# ForEK2.net
KiCad netlist of a schematic drawn in Altium Designer
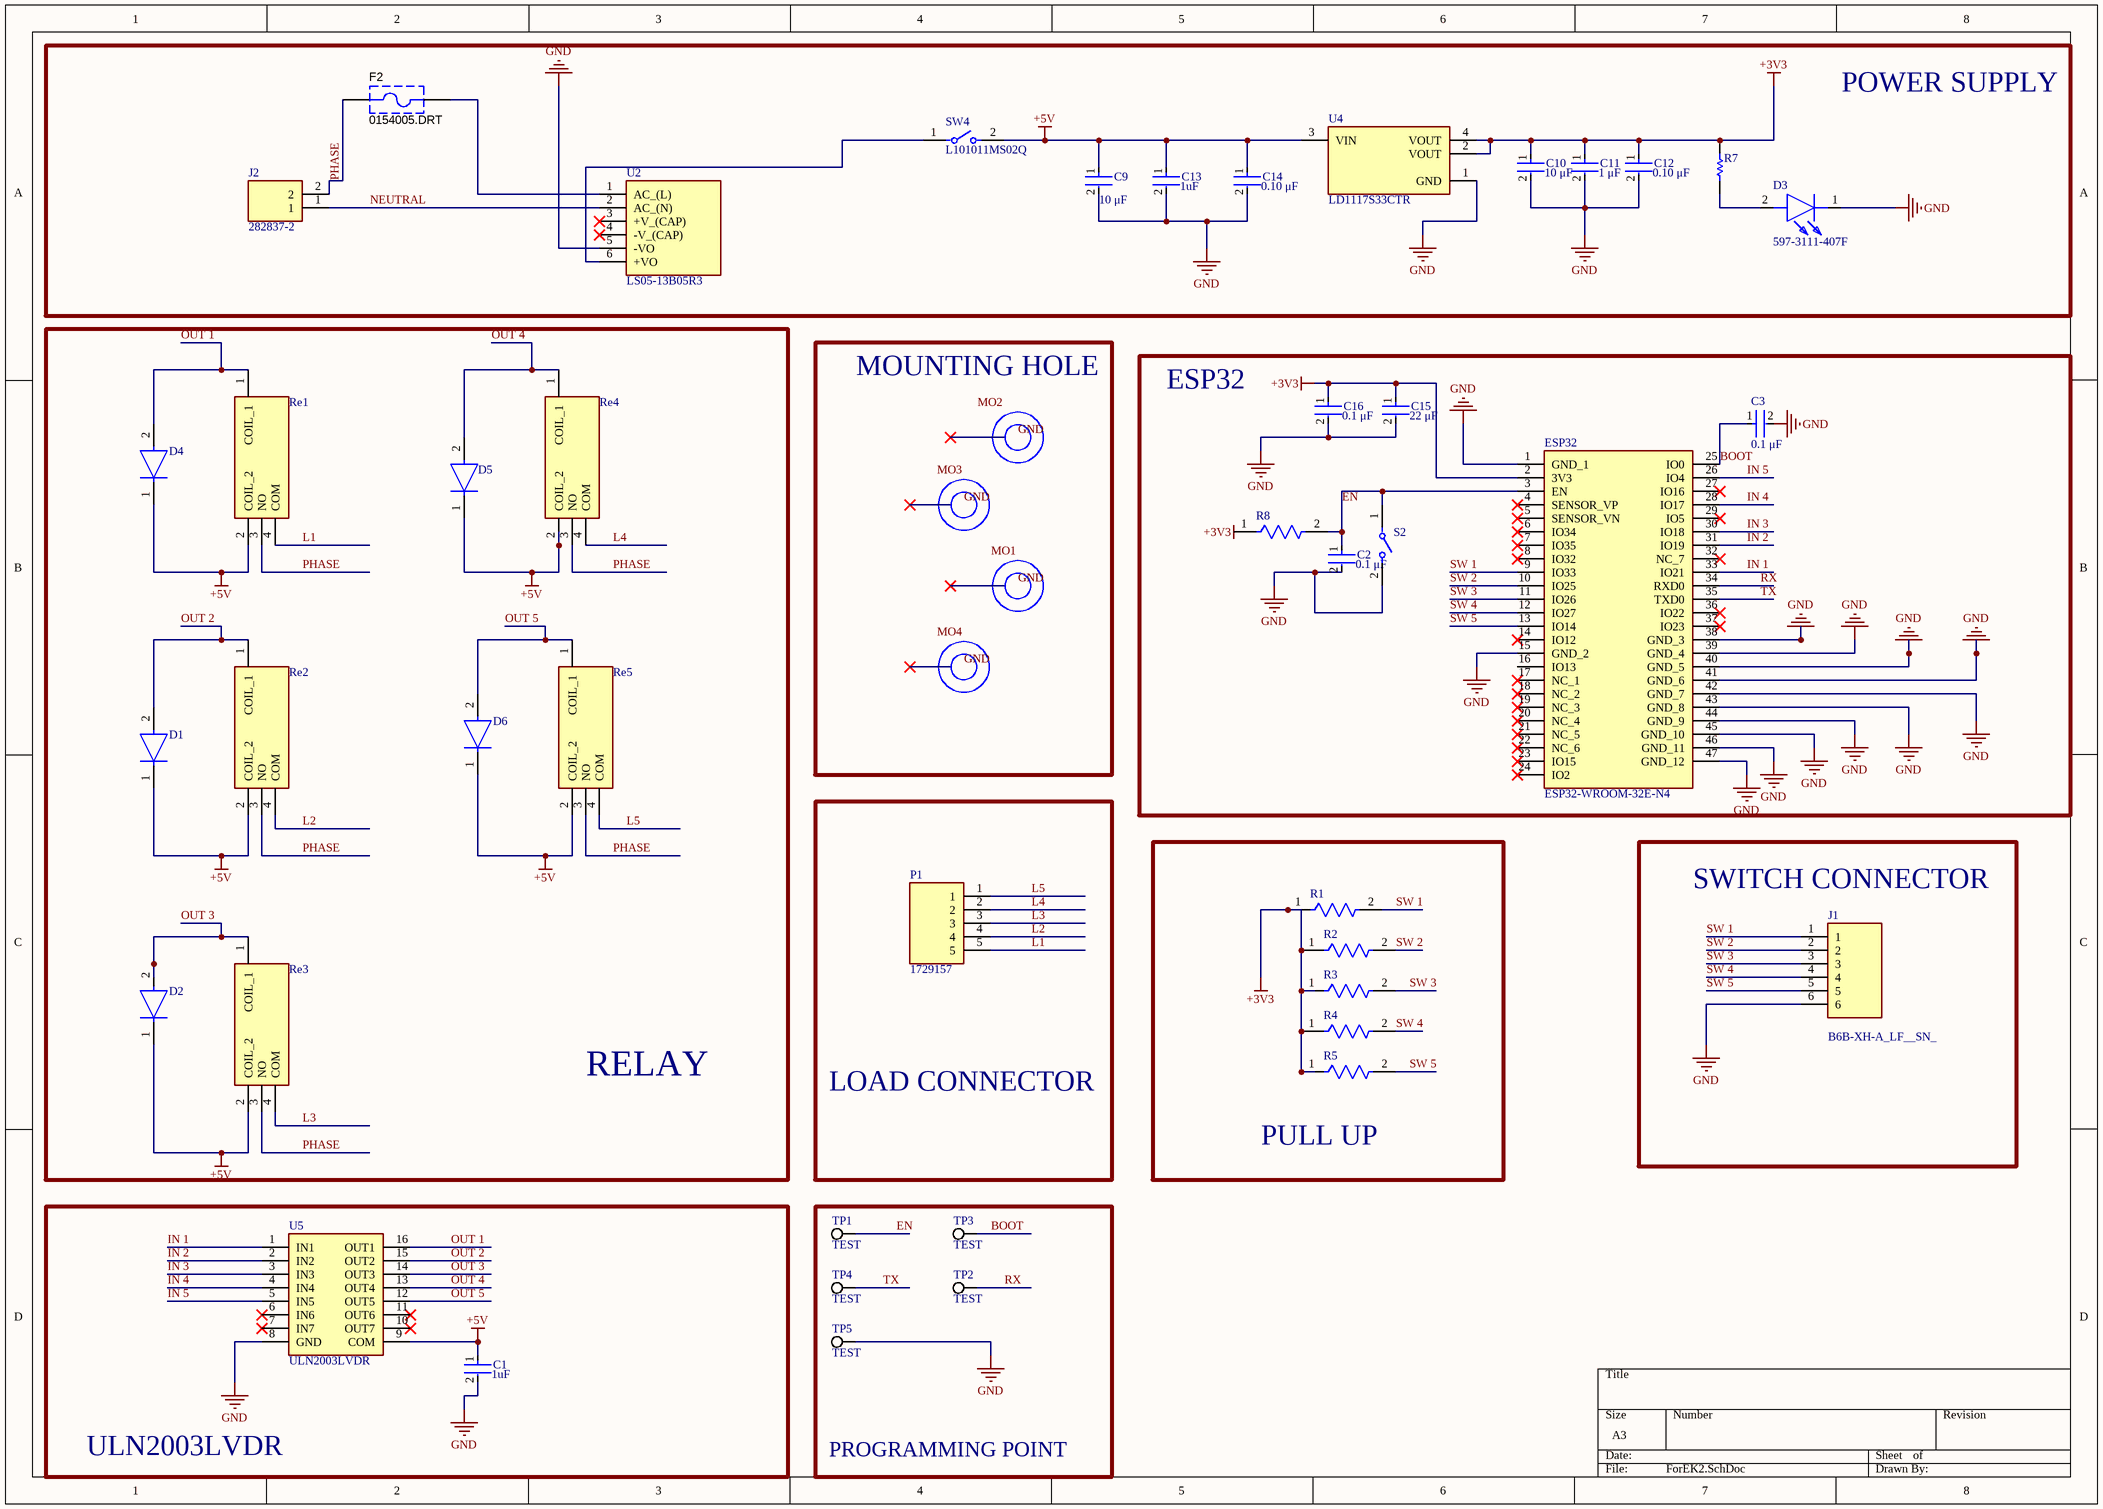
[diagram p0: ForEK2.SchDoc]

(export (version "E")
  (design (tool "Eeschema 10.0.6"))
  (components
    (comp (ref "C1")
      (value "C0402C104K8PACTU")
      (footprint "FP-C0402-BB-MFG")
      (description "CAP CER 0.1UF 10V X5R 0402")
      (fields
        (field (name "CAPACITANCE") "1uF")
        (field (name "MANUFACTURER") "Kemet")
        (field (name "TOLERANCE") "0.1")
      )
      (libsource (lib "Altium Content Vault") (part "b4654b650e69147ec39a6b967a45e02"))
    )
    (comp (ref "C2")
      (value "0.1 μF")
      (footprint "FP-C0402-BB-MFG")
      (description "CAP CER 0.1UF 10V X5R 0402")
      (fields (field (name "MANUFACTURER") "Kemet") (field (name "TOLERANCE") "0.1"))
      (libsource (lib "Altium Content Vault") (part "b4654b650e69147ec39a6b967a45e02"))
    )
    (comp (ref "C3")
      (value "0.1 μF")
      (footprint "FP-C0402-BB-MFG")
      (description "CAP CER 0.1UF 10V X5R 0402")
      (fields (field (name "MANUFACTURER") "Kemet") (field (name "TOLERANCE") "0.1"))
      (libsource (lib "Altium Content Vault") (part "b4654b650e69147ec39a6b967a45e02"))
    )
    (comp (ref "C9")
      (value "10 μF")
      (footprint "FP-C0402-BB-MFG")
      (description "CAP CER 0.1UF 10V X5R 0402")
      (fields (field (name "MANUFACTURER") "Kemet") (field (name "TOLERANCE") "0.1"))
      (libsource (lib "Altium Content Vault") (part "b4654b650e69147ec39a6b967a45e02"))
    )
    (comp (ref "C10")
      (value "10 μF")
      (footprint "FP-C0402-BB-MFG")
      (description "CAP CER 0.1UF 10V X5R 0402")
      (fields (field (name "MANUFACTURER") "Kemet") (field (name "TOLERANCE") "0.1"))
      (libsource (lib "Altium Content Vault") (part "b4654b650e69147ec39a6b967a45e02"))
    )
    (comp (ref "C11")
      (value "1 μF")
      (footprint "FP-C0402-BB-MFG")
      (description "CAP CER 0.1UF 10V X5R 0402")
      (fields (field (name "MANUFACTURER") "Kemet") (field (name "TOLERANCE") "0.1"))
      (libsource (lib "Altium Content Vault") (part "b4654b650e69147ec39a6b967a45e02"))
    )
    (comp (ref "C12")
      (value "C0402C104K8PACTU")
      (footprint "FP-C0402-BB-MFG")
      (description "CAP CER 0.1UF 10V X5R 0402")
      (fields
        (field (name "CAPACITANCE") "0.10 μF")
        (field (name "MANUFACTURER") "Kemet")
        (field (name "TOLERANCE") "0.1")
      )
      (libsource (lib "Altium Content Vault") (part "b4654b650e69147ec39a6b967a45e02"))
    )
    (comp (ref "C13")
      (value "C0402C104K8PACTU")
      (footprint "FP-C0402-BB-MFG")
      (description "CAP CER 0.1UF 10V X5R 0402")
      (fields
        (field (name "CAPACITANCE") "1uF")
        (field (name "MANUFACTURER") "Kemet")
        (field (name "TOLERANCE") "0.1")
      )
      (libsource (lib "Altium Content Vault") (part "b4654b650e69147ec39a6b967a45e02"))
    )
    (comp (ref "C14")
      (value "0.10 μF")
      (footprint "FP-C0402-BB-MFG")
      (description "CAP CER 0.1UF 10V X5R 0402")
      (fields (field (name "MANUFACTURER") "Kemet") (field (name "TOLERANCE") "0.1"))
      (libsource (lib "Altium Content Vault") (part "b4654b650e69147ec39a6b967a45e02"))
    )
    (comp (ref "C15")
      (value "22 μF")
      (footprint "FP-C0402-BB-MFG")
      (description "CAP CER 0.1UF 10V X5R 0402")
      (fields (field (name "MANUFACTURER") "Kemet") (field (name "TOLERANCE") "0.1"))
      (libsource (lib "Altium Content Vault") (part "b4654b650e69147ec39a6b967a45e02"))
    )
    (comp (ref "C16")
      (value "0.1 μF")
      (footprint "FP-C0402-BB-MFG")
      (description "CAP CER 0.1UF 10V X5R 0402")
      (fields (field (name "MANUFACTURER") "Kemet") (field (name "TOLERANCE") "0.1"))
      (libsource (lib "Altium Content Vault") (part "b4654b650e69147ec39a6b967a45e02"))
    )
    (comp (ref "D1")
      (value "1N4148")
      (footprint "FP-017AG-MFG")
      (description "DIODE GEN PURP 100V 200MA DO35")
      (fields (field (name "VOLTAGE") "100V"))
      (libsource (lib "Altium Content Vault") (part "d7152d700b627762746794eb795d46e"))
    )
    (comp (ref "D2")
      (value "1N4148")
      (footprint "FP-017AG-MFG")
      (description "DIODE GEN PURP 100V 200MA DO35")
      (fields (field (name "VOLTAGE") "100V"))
      (libsource (lib "Altium Content Vault") (part "d7152d700b627762746794eb795d46e"))
    )
    (comp (ref "D3")
      (value "597-3111-407F")
      (footprint "SamacSys:LEDC3015X150N")
      (description "LED")
      (fields (field (name "MOUSER PART NUMBER") "645-597-3111-407F"))
      (libsource (lib "*") (part "597-3111-407F"))
    )
    (comp (ref "D4")
      (value "1N4148")
      (footprint "FP-017AG-MFG")
      (description "DIODE GEN PURP 100V 200MA DO35")
      (fields (field (name "VOLTAGE") "100V"))
      (libsource (lib "Altium Content Vault") (part "d7152d700b627762746794eb795d46e"))
    )
    (comp (ref "D5")
      (value "1N4148")
      (footprint "FP-017AG-MFG")
      (description "DIODE GEN PURP 100V 200MA DO35")
      (fields (field (name "VOLTAGE") "100V"))
      (libsource (lib "Altium Content Vault") (part "d7152d700b627762746794eb795d46e"))
    )
    (comp (ref "D6")
      (value "1N4148")
      (footprint "FP-017AG-MFG")
      (description "DIODE GEN PURP 100V 200MA DO35")
      (fields (field (name "VOLTAGE") "100V"))
      (libsource (lib "Altium Content Vault") (part "d7152d700b627762746794eb795d46e"))
    )
    (comp (ref "ESP32")
      (value "ESP32-WROOM-32E-N4")
      (footprint "SamacSys:ESP32WROOM32EN4")
      (description "Integrated Circuit")
      (fields (field (name "MOUSER PART NUMBER") "356-ESP32WRM32E132PH"))
      (libsource (lib "*") (part "ESP32-WROOM-32E-N4"))
    )
    (comp (ref "F2")
      (value "0154005.DRT")
      (footprint "LFUS-154_V")
      (description "Fuse and Holder Combination, 125 V, 5 A, -55 to 125 degC, 2-Pin SMD, RoHS, Tape and Reel")
      (fields (field (name "MANUFACTURER") "Littelfuse"))
      (libsource (lib "Altium Content Vault") (part "FUSE_HOLDER-2"))
    )
    (comp (ref "J1")
      (value "B6B-XH-A_LF__SN_")
      (footprint "SamacSys:SHDR6W64P0X250_1X6_1740X575X700P")
      (description "Connector")
      (fields
        (field (name "MANUFACTURER_PART_NUMBER") "B6B-XH-A(LF)(SN)")
        (field (name "MOUSER PART NUMBER") "306-B6BXHALFSN")
      )
      (libsource (lib "*") (part "B6B-XH-A_LF__SN_"))
    )
    (comp (ref "J2")
      (value "282837-2")
      (footprint "SamacSys:2828372")
      (description "Connector")
      (fields (field (name "MOUSER PART NUMBER") "571-2828372"))
      (libsource (lib "*") (part "282837-2"))
    )
    (comp (ref "P1")
      (value "1729157")
      (footprint "SamacSys:1729157")
      (description "Connector")
      (fields (field (name "MOUSER PART NUMBER") "651-1729157"))
      (libsource (lib "*") (part "1729157"))
    )
    (comp (ref "R1")
      (value "CRCW040210K0JNED")
      (footprint "FP-CRCW0402-e3-IPC_B")
      (description "RES Thick Film, 10kΩ, 5%, 0.063W, 200ppm/°C, 0402")
      (fields (field (name "TOLERANCE") "5%"))
      (libsource (lib "Altium Content Vault") (part "1029c3af85768c4190bb7ad29bc67b5"))
    )
    (comp (ref "R2")
      (value "CRCW040210K0JNED")
      (footprint "FP-CRCW0402-e3-IPC_B")
      (description "RES Thick Film, 10kΩ, 5%, 0.063W, 200ppm/°C, 0402")
      (fields (field (name "TOLERANCE") "5%"))
      (libsource (lib "Altium Content Vault") (part "1029c3af85768c4190bb7ad29bc67b5"))
    )
    (comp (ref "R3")
      (value "CRCW040210K0JNED")
      (footprint "FP-CRCW0402-e3-IPC_B")
      (description "RES Thick Film, 10kΩ, 5%, 0.063W, 200ppm/°C, 0402")
      (fields (field (name "TOLERANCE") "5%"))
      (libsource (lib "Altium Content Vault") (part "1029c3af85768c4190bb7ad29bc67b5"))
    )
    (comp (ref "R4")
      (value "CRCW040210K0JNED")
      (footprint "FP-CRCW0402-e3-IPC_B")
      (description "RES Thick Film, 10kΩ, 5%, 0.063W, 200ppm/°C, 0402")
      (fields (field (name "TOLERANCE") "5%"))
      (libsource (lib "Altium Content Vault") (part "1029c3af85768c4190bb7ad29bc67b5"))
    )
    (comp (ref "R5")
      (value "CRCW040210K0JNED")
      (footprint "FP-CRCW0402-e3-IPC_B")
      (description "RES Thick Film, 10kΩ, 5%, 0.063W, 200ppm/°C, 0402")
      (fields (field (name "TOLERANCE") "5%"))
      (libsource (lib "Altium Content Vault") (part "1029c3af85768c4190bb7ad29bc67b5"))
    )
    (comp (ref "R7")
      (value "ERJ-3EKF3300V")
      (footprint "RESC1608X55X30LL15T15")
      (description "Chip Resistor, 330 Ohm, +/- 1%, 0.1 W, -55 to 155 degC, 0603 (1608 Metric), RoHS, Tape and Reel")
      (libsource (lib "Altium Content Vault") (part "RES-2"))
    )
    (comp (ref "R8")
      (value "CRCW040210K0JNED")
      (footprint "FP-CRCW0402-e3-IPC_B")
      (description "RES Thick Film, 10kΩ, 5%, 0.063W, 200ppm/°C, 0402")
      (fields (field (name "TOLERANCE") "5%"))
      (libsource (lib "Altium Content Vault") (part "1029c3af85768c4190bb7ad29bc67b5"))
    )
    (comp (ref "Re1")
      (value "HF46F-G_5-HS1T")
      (footprint "SamacSys:HF46FG5HS1T")
      (description "Relay or Contactor")
      (fields (field (name "MANUFACTURER_PART_NUMBER") "HF46F-G/5-HS1T"))
      (libsource (lib "*") (part "HF46F-G_5-HS1T"))
    )
    (comp (ref "Re2")
      (value "HF46F-G_5-HS1T")
      (footprint "SamacSys:HF46FG5HS1T")
      (description "Relay or Contactor")
      (fields (field (name "MANUFACTURER_PART_NUMBER") "HF46F-G/5-HS1T"))
      (libsource (lib "*") (part "HF46F-G_5-HS1T"))
    )
    (comp (ref "Re3")
      (value "HF46F-G_5-HS1T")
      (footprint "SamacSys:HF46FG5HS1T")
      (description "Relay or Contactor")
      (fields (field (name "MANUFACTURER_PART_NUMBER") "HF46F-G/5-HS1T"))
      (libsource (lib "*") (part "HF46F-G_5-HS1T"))
    )
    (comp (ref "Re4")
      (value "HF46F-G_5-HS1T")
      (footprint "SamacSys:HF46FG5HS1T")
      (description "Relay or Contactor")
      (fields (field (name "MANUFACTURER_PART_NUMBER") "HF46F-G/5-HS1T"))
      (libsource (lib "*") (part "HF46F-G_5-HS1T"))
    )
    (comp (ref "Re5")
      (value "HF46F-G_5-HS1T")
      (footprint "SamacSys:HF46FG5HS1T")
      (description "Relay or Contactor")
      (fields (field (name "MANUFACTURER_PART_NUMBER") "HF46F-G/5-HS1T"))
      (libsource (lib "*") (part "HF46F-G_5-HS1T"))
    )
    (comp (ref "S2")
      (value "L101011MS02Q")
      (footprint "FP-L101011MS02Q-MFG")
      (description "SWITCH SLIDE SPST 4A 125V")
      (libsource (lib "Altium Content Vault") (part "bb27bde45df87f1f469753f287ef5ae"))
    )
    (comp (ref "SW4")
      (value "L101011MS02Q")
      (footprint "FP-L101011MS02Q-MFG")
      (description "SWITCH SLIDE SPST 4A 125V")
      (libsource (lib "Altium Content Vault") (part "bb27bde45df87f1f469753f287ef5ae"))
    )
    (comp (ref "TP1")
      (value "TEST")
      (footprint "KSTN-5012_V")
      (description "Test Point, White, Through Hole, RoHS, Bulk")
      (fields (field (name "MANUFACTURER") "Keystone"))
      (libsource (lib "Altium Content Vault") (part "TESTPOINT_WHITE"))
    )
    (comp (ref "TP2")
      (value "TEST")
      (footprint "KSTN-5012_V")
      (description "Test Point, White, Through Hole, RoHS, Bulk")
      (fields (field (name "MANUFACTURER") "Keystone"))
      (libsource (lib "Altium Content Vault") (part "TESTPOINT_WHITE"))
    )
    (comp (ref "TP3")
      (value "TEST")
      (footprint "KSTN-5012_V")
      (description "Test Point, White, Through Hole, RoHS, Bulk")
      (fields (field (name "MANUFACTURER") "Keystone"))
      (libsource (lib "Altium Content Vault") (part "TESTPOINT_WHITE"))
    )
    (comp (ref "TP4")
      (value "TEST")
      (footprint "KSTN-5012_V")
      (description "Test Point, White, Through Hole, RoHS, Bulk")
      (fields (field (name "MANUFACTURER") "Keystone"))
      (libsource (lib "Altium Content Vault") (part "TESTPOINT_WHITE"))
    )
    (comp (ref "TP5")
      (value "TEST")
      (footprint "KSTN-5012_V")
      (description "Test Point, White, Through Hole, RoHS, Bulk")
      (fields (field (name "MANUFACTURER") "Keystone"))
      (libsource (lib "Altium Content Vault") (part "TESTPOINT_WHITE"))
    )
    (comp (ref "U2")
      (value "LS05-13B05R3")
      (footprint "SamacSys:LS0513B05R3")
      (description "Power Supply")
      (libsource (lib "*") (part "LS05-13B05R3"))
    )
    (comp (ref "U4")
      (value "LD1117S33CTR")
      (footprint "FP-SOT-223-0046067_14-MFG")
      (description "IC REG LINEAR 3.3V 800MA SOT223")
      (libsource (lib "Altium Content Vault") (part "7818869c5c16ceab15634627166a29d"))
    )
    (comp (ref "U5")
      (value "ULN2003LVDR")
      (footprint "SamacSys:SOIC127P600X175-16N")
      (description "Integrated Circuit")
      (fields (field (name "MOUSER PART NUMBER") "595-ULN2003LVDR"))
      (libsource (lib "*") (part "ULN2003LVDR"))
    )
  )
  (nets
    (net (code "1") (name "+3V3") (class "Default")
      (node (ref "C10") (pin "1") (pinfunction "1_1") (pintype "passive"))
      (node (ref "C11") (pin "1") (pinfunction "1_1") (pintype "passive"))
      (node (ref "C12") (pin "1") (pinfunction "1_1") (pintype "passive"))
      (node (ref "C15") (pin "1") (pinfunction "1_1") (pintype "passive"))
      (node (ref "C16") (pin "1") (pinfunction "1_1") (pintype "passive"))
      (node (ref "ESP32") (pin "2") (pinfunction "3V3_2") (pintype "passive"))
      (node (ref "R1") (pin "1") (pinfunction "1_1") (pintype "passive"))
      (node (ref "R2") (pin "1") (pinfunction "1_1") (pintype "passive"))
      (node (ref "R3") (pin "1") (pinfunction "1_1") (pintype "passive"))
      (node (ref "R4") (pin "1") (pinfunction "1_1") (pintype "passive"))
      (node (ref "R5") (pin "1") (pinfunction "1_1") (pintype "passive"))
      (node (ref "R7") (pin "2") (pinfunction "2_2") (pintype "passive"))
      (node (ref "U4") (pin "2") (pinfunction "VOUT_2") (pintype "power_in"))
      (node (ref "U4") (pin "4") (pinfunction "VOUT_4") (pintype "power_in"))
    )
    (net (code "2") (name "+5V") (class "Default")
      (node (ref "C1") (pin "1") (pinfunction "1_1") (pintype "passive"))
      (node (ref "C13") (pin "1") (pinfunction "1_1") (pintype "passive"))
      (node (ref "C14") (pin "1") (pinfunction "1_1") (pintype "passive"))
      (node (ref "C9") (pin "1") (pinfunction "1_1") (pintype "passive"))
      (node (ref "D1") (pin "1") (pinfunction "C_1") (pintype "passive"))
      (node (ref "D2") (pin "1") (pinfunction "C_1") (pintype "passive"))
      (node (ref "D4") (pin "1") (pinfunction "C_1") (pintype "passive"))
      (node (ref "D5") (pin "1") (pinfunction "C_1") (pintype "passive"))
      (node (ref "D6") (pin "1") (pinfunction "C_1") (pintype "passive"))
      (node (ref "Re1") (pin "2") (pinfunction "COIL_2_2") (pintype "passive"))
      (node (ref "Re2") (pin "2") (pinfunction "COIL_2_2") (pintype "passive"))
      (node (ref "Re3") (pin "2") (pinfunction "COIL_2_2") (pintype "passive"))
      (node (ref "Re4") (pin "2") (pinfunction "COIL_2_2") (pintype "passive"))
      (node (ref "Re5") (pin "2") (pinfunction "COIL_2_2") (pintype "passive"))
      (node (ref "SW4") (pin "2") (pinfunction "2_2") (pintype "passive"))
      (node (ref "U4") (pin "3") (pinfunction "VIN_3") (pintype "power_in"))
      (node (ref "U5") (pin "9") (pinfunction "COM_9") (pintype "passive"))
    )
    (net (code "3") (name "/BOOT") (class "Default")
      (node (ref "C3") (pin "1") (pinfunction "1_1") (pintype "passive"))
      (node (ref "ESP32") (pin "25") (pinfunction "IO0_25") (pintype "passive"))
      (node (ref "TP3") (pin "1") (pinfunction "1_1") (pintype "passive"))
    )
    (net (code "4") (name "/EN") (class "Default")
      (node (ref "C2") (pin "1") (pinfunction "1_1") (pintype "passive"))
      (node (ref "ESP32") (pin "3") (pinfunction "EN_3") (pintype "passive"))
      (node (ref "R8") (pin "2") (pinfunction "2_2") (pintype "passive"))
      (node (ref "S2") (pin "1") (pinfunction "1_1") (pintype "passive"))
      (node (ref "TP1") (pin "1") (pinfunction "1_1") (pintype "passive"))
    )
    (net (code "5") (name "/IN 1") (class "Default")
      (node (ref "ESP32") (pin "33") (pinfunction "IO21_33") (pintype "passive"))
      (node (ref "U5") (pin "1") (pinfunction "IN1_1") (pintype "passive"))
    )
    (net (code "6") (name "/IN 2") (class "Default")
      (node (ref "ESP32") (pin "31") (pinfunction "IO19_31") (pintype "passive"))
      (node (ref "U5") (pin "2") (pinfunction "IN2_2") (pintype "passive"))
    )
    (net (code "7") (name "/IN 3") (class "Default")
      (node (ref "ESP32") (pin "30") (pinfunction "IO18_30") (pintype "passive"))
      (node (ref "U5") (pin "3") (pinfunction "IN3_3") (pintype "passive"))
    )
    (net (code "8") (name "/IN 4") (class "Default")
      (node (ref "ESP32") (pin "28") (pinfunction "IO17_28") (pintype "passive"))
      (node (ref "U5") (pin "4") (pinfunction "IN4_4") (pintype "passive"))
    )
    (net (code "9") (name "/IN 5") (class "Default")
      (node (ref "ESP32") (pin "26") (pinfunction "IO4_26") (pintype "passive"))
      (node (ref "U5") (pin "5") (pinfunction "IN5_5") (pintype "passive"))
    )
    (net (code "10") (name "/L1") (class "Default")
      (node (ref "P1") (pin "5") (pinfunction "5_5") (pintype "passive"))
      (node (ref "Re1") (pin "4") (pinfunction "COM_4") (pintype "passive"))
    )
    (net (code "11") (name "/L2") (class "Default")
      (node (ref "P1") (pin "4") (pinfunction "4_4") (pintype "passive"))
      (node (ref "Re2") (pin "4") (pinfunction "COM_4") (pintype "passive"))
    )
    (net (code "12") (name "/L3") (class "Default")
      (node (ref "P1") (pin "3") (pinfunction "3_3") (pintype "passive"))
      (node (ref "Re3") (pin "4") (pinfunction "COM_4") (pintype "passive"))
    )
    (net (code "13") (name "/L4") (class "Default")
      (node (ref "P1") (pin "2") (pinfunction "2_2") (pintype "passive"))
      (node (ref "Re4") (pin "4") (pinfunction "COM_4") (pintype "passive"))
    )
    (net (code "14") (name "/L5") (class "Default")
      (node (ref "P1") (pin "1") (pinfunction "1_1") (pintype "passive"))
      (node (ref "Re5") (pin "4") (pinfunction "COM_4") (pintype "passive"))
    )
    (net (code "19") (name "/NEUTRAL") (class "Default")
      (node (ref "J2") (pin "1") (pinfunction "1_1") (pintype "passive"))
      (node (ref "U2") (pin "2") (pinfunction "AC_(N)_2") (pintype "passive"))
    )
    (net (code "20") (name "/OUT 1") (class "Default")
      (node (ref "D4") (pin "2") (pinfunction "A_2") (pintype "passive"))
      (node (ref "Re1") (pin "1") (pinfunction "COIL_1_1") (pintype "passive"))
      (node (ref "U5") (pin "16") (pinfunction "OUT1_16") (pintype "passive"))
    )
    (net (code "21") (name "/OUT 2") (class "Default")
      (node (ref "D1") (pin "2") (pinfunction "A_2") (pintype "passive"))
      (node (ref "Re2") (pin "1") (pinfunction "COIL_1_1") (pintype "passive"))
      (node (ref "U5") (pin "15") (pinfunction "OUT2_15") (pintype "passive"))
    )
    (net (code "22") (name "/OUT 3") (class "Default")
      (node (ref "D2") (pin "2") (pinfunction "A_2") (pintype "passive"))
      (node (ref "Re3") (pin "1") (pinfunction "COIL_1_1") (pintype "passive"))
      (node (ref "U5") (pin "14") (pinfunction "OUT3_14") (pintype "passive"))
    )
    (net (code "23") (name "/OUT 4") (class "Default")
      (node (ref "D5") (pin "2") (pinfunction "A_2") (pintype "passive"))
      (node (ref "Re4") (pin "1") (pinfunction "COIL_1_1") (pintype "passive"))
      (node (ref "U5") (pin "13") (pinfunction "OUT4_13") (pintype "passive"))
    )
    (net (code "24") (name "/OUT 5") (class "Default")
      (node (ref "D6") (pin "2") (pinfunction "A_2") (pintype "passive"))
      (node (ref "Re5") (pin "1") (pinfunction "COIL_1_1") (pintype "passive"))
      (node (ref "U5") (pin "12") (pinfunction "OUT5_12") (pintype "passive"))
    )
    (net (code "25") (name "/PHASE") (class "Default")
      (node (ref "F2") (pin "1") (pinfunction "1_1") (pintype "passive"))
      (node (ref "J2") (pin "2") (pinfunction "2_2") (pintype "passive"))
      (node (ref "Re1") (pin "3") (pinfunction "NO_3") (pintype "passive"))
      (node (ref "Re2") (pin "3") (pinfunction "NO_3") (pintype "passive"))
      (node (ref "Re3") (pin "3") (pinfunction "NO_3") (pintype "passive"))
      (node (ref "Re4") (pin "3") (pinfunction "NO_3") (pintype "passive"))
      (node (ref "Re5") (pin "3") (pinfunction "NO_3") (pintype "passive"))
    )
    (net (code "26") (name "/RX") (class "Default")
      (node (ref "ESP32") (pin "34") (pinfunction "RXD0_34") (pintype "passive"))
      (node (ref "TP2") (pin "1") (pinfunction "1_1") (pintype "passive"))
    )
    (net (code "27") (name "/SW 1") (class "Default")
      (node (ref "ESP32") (pin "9") (pinfunction "IO33_9") (pintype "passive"))
      (node (ref "J1") (pin "1") (pinfunction "1_1") (pintype "passive"))
      (node (ref "R1") (pin "2") (pinfunction "2_2") (pintype "passive"))
    )
    (net (code "28") (name "/SW 2") (class "Default")
      (node (ref "ESP32") (pin "10") (pinfunction "IO25_10") (pintype "passive"))
      (node (ref "J1") (pin "2") (pinfunction "2_2") (pintype "passive"))
      (node (ref "R2") (pin "2") (pinfunction "2_2") (pintype "passive"))
    )
    (net (code "29") (name "/SW 3") (class "Default")
      (node (ref "ESP32") (pin "11") (pinfunction "IO26_11") (pintype "passive"))
      (node (ref "J1") (pin "3") (pinfunction "3_3") (pintype "passive"))
      (node (ref "R3") (pin "2") (pinfunction "2_2") (pintype "passive"))
    )
    (net (code "30") (name "/SW 4") (class "Default")
      (node (ref "ESP32") (pin "12") (pinfunction "IO27_12") (pintype "passive"))
      (node (ref "J1") (pin "4") (pinfunction "4_4") (pintype "passive"))
      (node (ref "R4") (pin "2") (pinfunction "2_2") (pintype "passive"))
    )
    (net (code "31") (name "/SW 5") (class "Default")
      (node (ref "ESP32") (pin "13") (pinfunction "IO14_13") (pintype "passive"))
      (node (ref "J1") (pin "5") (pinfunction "5_5") (pintype "passive"))
      (node (ref "R5") (pin "2") (pinfunction "2_2") (pintype "passive"))
    )
    (net (code "32") (name "/TX") (class "Default")
      (node (ref "ESP32") (pin "35") (pinfunction "TXD0_35") (pintype "passive"))
      (node (ref "TP4") (pin "1") (pinfunction "1_1") (pintype "passive"))
    )
    (net (code "33") (name "GND") (class "Default")
      (node (ref "C1") (pin "2") (pinfunction "2_2") (pintype "passive"))
      (node (ref "C10") (pin "2") (pinfunction "2_2") (pintype "passive"))
      (node (ref "C11") (pin "2") (pinfunction "2_2") (pintype "passive"))
      (node (ref "C12") (pin "2") (pinfunction "2_2") (pintype "passive"))
      (node (ref "C13") (pin "2") (pinfunction "2_2") (pintype "passive"))
      (node (ref "C14") (pin "2") (pinfunction "2_2") (pintype "passive"))
      (node (ref "C15") (pin "2") (pinfunction "2_2") (pintype "passive"))
      (node (ref "C16") (pin "2") (pinfunction "2_2") (pintype "passive"))
      (node (ref "C2") (pin "2") (pinfunction "2_2") (pintype "passive"))
      (node (ref "C3") (pin "2") (pinfunction "2_2") (pintype "passive"))
      (node (ref "C9") (pin "2") (pinfunction "2_2") (pintype "passive"))
      (node (ref "D3") (pin "1") (pinfunction "K_1") (pintype "passive"))
      (node (ref "ESP32") (pin "1") (pinfunction "GND_1_1") (pintype "passive"))
      (node (ref "ESP32") (pin "15") (pinfunction "GND_2_15") (pintype "passive"))
      (node (ref "ESP32") (pin "38") (pinfunction "GND_3_38") (pintype "passive"))
      (node (ref "ESP32") (pin "39") (pinfunction "GND_4_39") (pintype "passive"))
      (node (ref "ESP32") (pin "40") (pinfunction "GND_5_40") (pintype "passive"))
      (node (ref "ESP32") (pin "41") (pinfunction "GND_6_41") (pintype "passive"))
      (node (ref "ESP32") (pin "42") (pinfunction "GND_7_42") (pintype "passive"))
      (node (ref "ESP32") (pin "43") (pinfunction "GND_8_43") (pintype "passive"))
      (node (ref "ESP32") (pin "44") (pinfunction "GND_9_44") (pintype "passive"))
      (node (ref "ESP32") (pin "45") (pinfunction "GND_10_45") (pintype "passive"))
      (node (ref "ESP32") (pin "46") (pinfunction "GND_11_46") (pintype "passive"))
      (node (ref "ESP32") (pin "47") (pinfunction "GND_12_47") (pintype "passive"))
      (node (ref "J1") (pin "6") (pinfunction "6_6") (pintype "passive"))
      (node (ref "S2") (pin "2") (pinfunction "2_2") (pintype "passive"))
      (node (ref "TP5") (pin "1") (pinfunction "1_1") (pintype "passive"))
      (node (ref "U2") (pin "5") (pinfunction "-VO_5") (pintype "passive"))
      (node (ref "U4") (pin "1") (pinfunction "GND_1") (pintype "power_in"))
      (node (ref "U5") (pin "8") (pinfunction "GND_8") (pintype "passive"))
    )
    (net (code "34") (name "Net-(D3-A)") (class "Default")
      (node (ref "D3") (pin "2") (pinfunction "A_2") (pintype "passive"))
      (node (ref "R7") (pin "1") (pinfunction "1_1") (pintype "passive"))
    )
    (net (code "35") (name "Net-(U2-+VO)") (class "Default")
      (node (ref "SW4") (pin "1") (pinfunction "1_1") (pintype "passive"))
      (node (ref "U2") (pin "6") (pinfunction "+VO_6") (pintype "passive"))
    )
    (net (code "36") (name "Net-(U2-AC_(L))") (class "Default")
      (node (ref "F2") (pin "2") (pinfunction "2_2") (pintype "passive"))
      (node (ref "U2") (pin "1") (pinfunction "AC_(L)_1") (pintype "passive"))
    )
    (net (code "37") (name "unconnected-(ESP32-IO2-Pad24)") (class "Default")
      (node (ref "ESP32") (pin "24") (pinfunction "IO2_24") (pintype "passive+no_connect"))
    )
    (net (code "38") (name "unconnected-(ESP32-IO5-Pad29)") (class "Default")
      (node (ref "ESP32") (pin "29") (pinfunction "IO5_29") (pintype "passive+no_connect"))
    )
    (net (code "39") (name "unconnected-(ESP32-IO12-Pad14)") (class "Default")
      (node (ref "ESP32") (pin "14") (pinfunction "IO12_14") (pintype "passive+no_connect"))
    )
    (net (code "40") (name "unconnected-(ESP32-IO13-Pad16)") (class "Default")
      (node (ref "ESP32") (pin "16") (pinfunction "IO13_16") (pintype "passive"))
    )
    (net (code "41") (name "unconnected-(ESP32-IO15-Pad23)") (class "Default")
      (node (ref "ESP32") (pin "23") (pinfunction "IO15_23") (pintype "passive+no_connect"))
    )
    (net (code "42") (name "unconnected-(ESP32-IO16-Pad27)") (class "Default")
      (node (ref "ESP32") (pin "27") (pinfunction "IO16_27") (pintype "passive+no_connect"))
    )
    (net (code "43") (name "unconnected-(ESP32-IO22-Pad36)") (class "Default")
      (node (ref "ESP32") (pin "36") (pinfunction "IO22_36") (pintype "passive+no_connect"))
    )
    (net (code "44") (name "unconnected-(ESP32-IO23-Pad37)") (class "Default")
      (node (ref "ESP32") (pin "37") (pinfunction "IO23_37") (pintype "passive+no_connect"))
    )
    (net (code "45") (name "unconnected-(ESP32-IO32-Pad8)") (class "Default")
      (node (ref "ESP32") (pin "8") (pinfunction "IO32_8") (pintype "passive+no_connect"))
    )
    (net (code "46") (name "unconnected-(ESP32-IO34-Pad6)") (class "Default")
      (node (ref "ESP32") (pin "6") (pinfunction "IO34_6") (pintype "passive+no_connect"))
    )
    (net (code "47") (name "unconnected-(ESP32-IO35-Pad7)") (class "Default")
      (node (ref "ESP32") (pin "7") (pinfunction "IO35_7") (pintype "passive+no_connect"))
    )
    (net (code "48") (name "unconnected-(ESP32-NC_1-Pad17)") (class "Default")
      (node (ref "ESP32") (pin "17") (pinfunction "NC_1_17") (pintype "passive+no_connect"))
    )
    (net (code "49") (name "unconnected-(ESP32-NC_2-Pad18)") (class "Default")
      (node (ref "ESP32") (pin "18") (pinfunction "NC_2_18") (pintype "passive+no_connect"))
    )
    (net (code "50") (name "unconnected-(ESP32-NC_3-Pad19)") (class "Default")
      (node (ref "ESP32") (pin "19") (pinfunction "NC_3_19") (pintype "passive+no_connect"))
    )
    (net (code "51") (name "unconnected-(ESP32-NC_4-Pad20)") (class "Default")
      (node (ref "ESP32") (pin "20") (pinfunction "NC_4_20") (pintype "passive+no_connect"))
    )
    (net (code "52") (name "unconnected-(ESP32-NC_5-Pad21)") (class "Default")
      (node (ref "ESP32") (pin "21") (pinfunction "NC_5_21") (pintype "passive+no_connect"))
    )
    (net (code "53") (name "unconnected-(ESP32-NC_6-Pad22)") (class "Default")
      (node (ref "ESP32") (pin "22") (pinfunction "NC_6_22") (pintype "passive+no_connect"))
    )
    (net (code "54") (name "unconnected-(ESP32-NC_7-Pad32)") (class "Default")
      (node (ref "ESP32") (pin "32") (pinfunction "NC_7_32") (pintype "passive+no_connect"))
    )
    (net (code "55") (name "unconnected-(ESP32-SENSOR_VN-Pad5)") (class "Default")
      (node (ref "ESP32") (pin "5") (pinfunction "SENSOR_VN_5") (pintype "passive+no_connect"))
    )
    (net (code "56") (name "unconnected-(ESP32-SENSOR_VP-Pad4)") (class "Default")
      (node (ref "ESP32") (pin "4") (pinfunction "SENSOR_VP_4") (pintype "passive+no_connect"))
    )
    (net (code "57") (name "unconnected-(R8-Pad1)") (class "Default")
      (node (ref "R8") (pin "1") (pinfunction "1_1") (pintype "passive"))
    )
    (net (code "58") (name "unconnected-(U2-+V_(CAP)-Pad3)") (class "Default")
      (node (ref "U2") (pin "3") (pinfunction "+V_(CAP)_3") (pintype "passive+no_connect"))
    )
    (net (code "59") (name "unconnected-(U2--V_(CAP)-Pad4)") (class "Default")
      (node (ref "U2") (pin "4") (pinfunction "-V_(CAP)_4") (pintype "passive+no_connect"))
    )
    (net (code "60") (name "unconnected-(U5-IN6-Pad6)") (class "Default")
      (node (ref "U5") (pin "6") (pinfunction "IN6_6") (pintype "passive+no_connect"))
    )
    (net (code "61") (name "unconnected-(U5-IN7-Pad7)") (class "Default")
      (node (ref "U5") (pin "7") (pinfunction "IN7_7") (pintype "passive+no_connect"))
    )
    (net (code "62") (name "unconnected-(U5-OUT6-Pad11)") (class "Default")
      (node (ref "U5") (pin "11") (pinfunction "OUT6_11") (pintype "passive+no_connect"))
    )
    (net (code "63") (name "unconnected-(U5-OUT7-Pad10)") (class "Default")
      (node (ref "U5") (pin "10") (pinfunction "OUT7_10") (pintype "passive+no_connect"))
    )
  )
)
